# Multiplier.net
KiCad netlist of a schematic drawn in Altium Designer
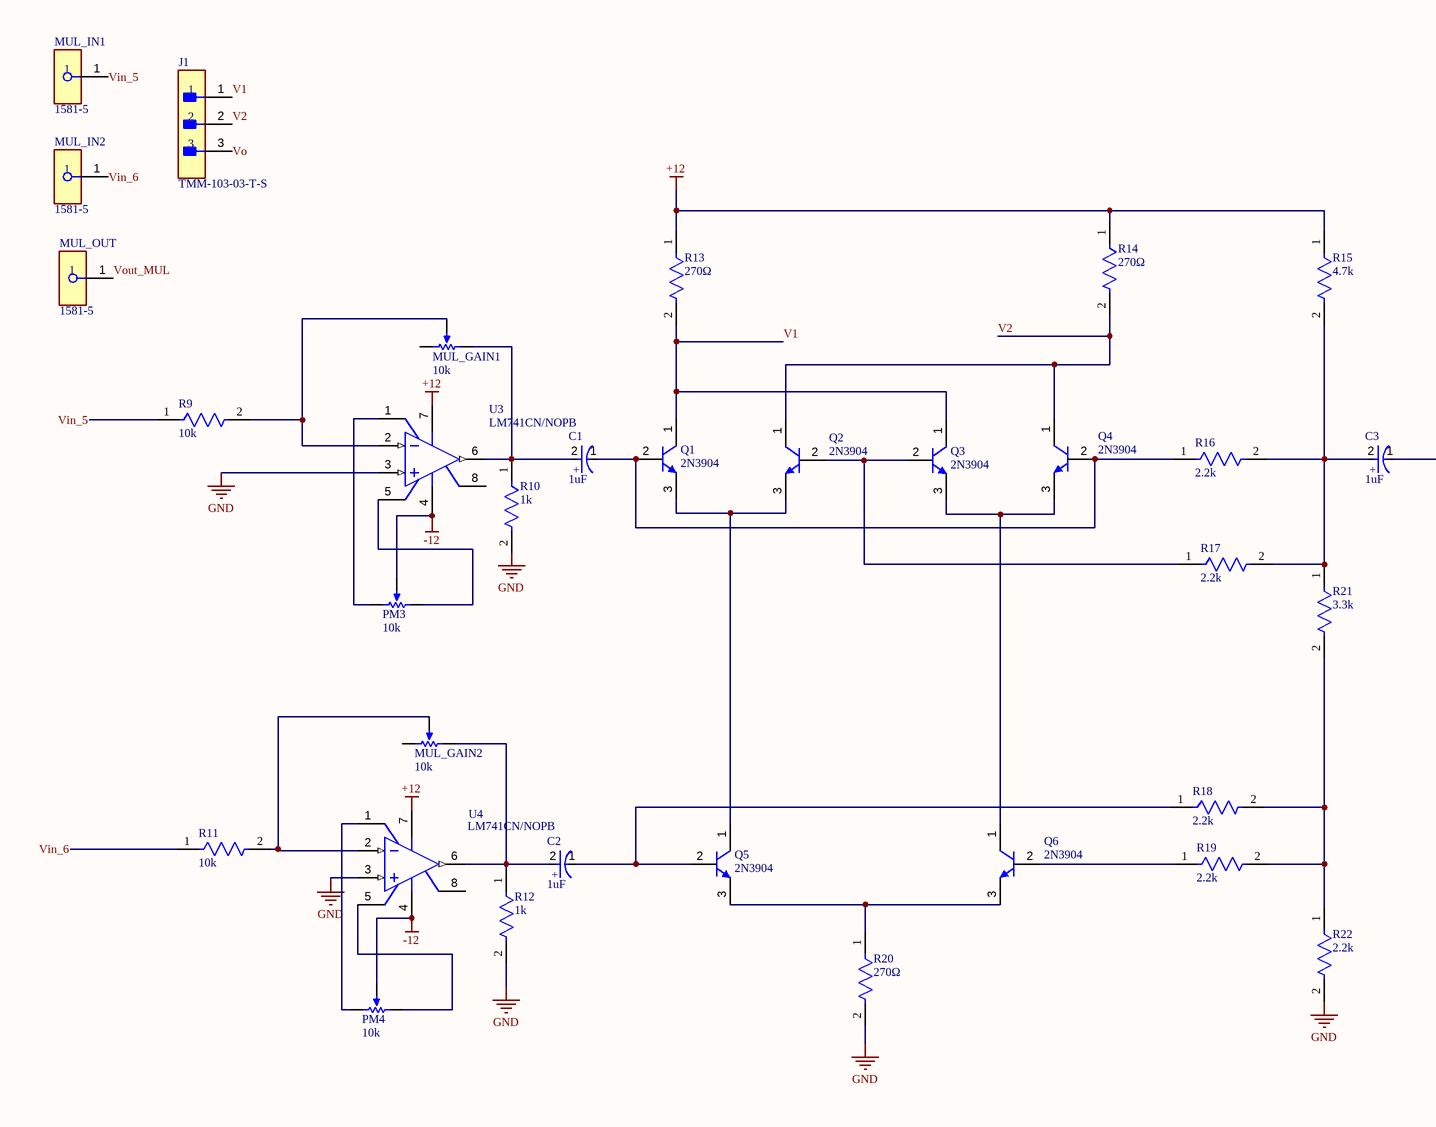
[diagram p0: Multiplier.SchDoc, left]
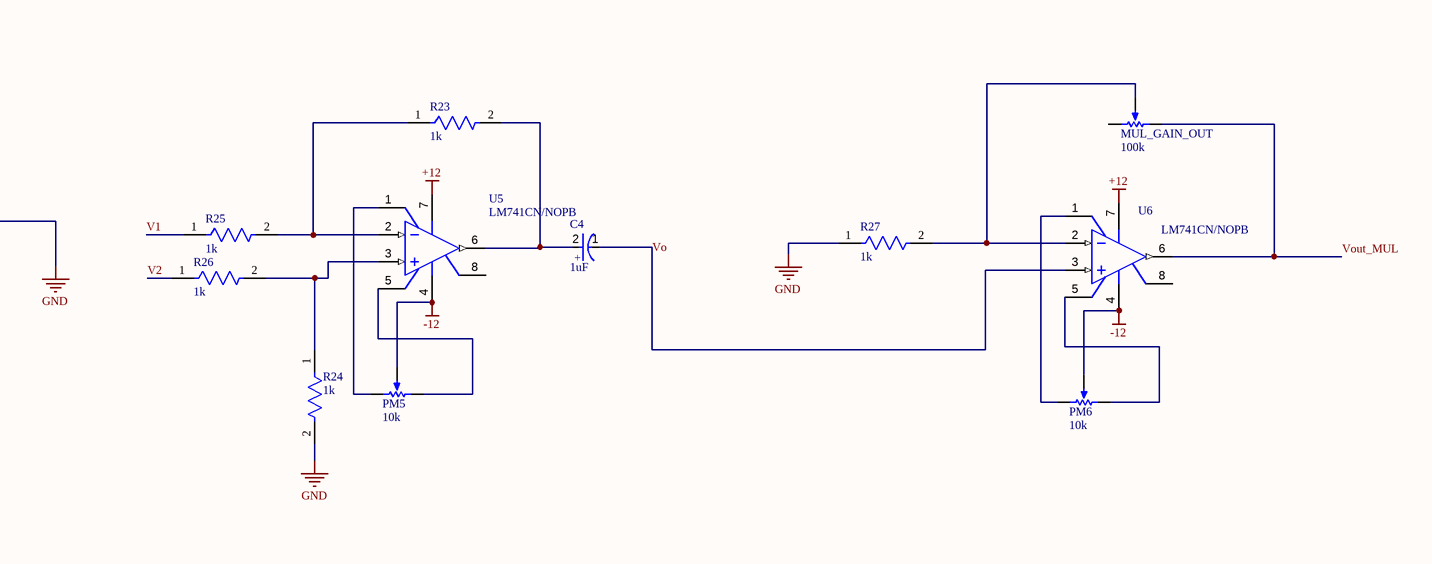
[diagram p1: Multiplier.SchDoc, right]

(export (version "E")
  (design (tool "Eeschema 10.0.6"))
  (components
    (comp (ref "C1")
      (value "1uF")
      (footprint "FP-ECA-2CHG010I-MFG")
      (description "CAP ALUM 1UF 20% 160V RADIAL")
      (fields (field (name "TOLERANCE") "20%"))
      (libsource (lib "Altium Content Vault") (part "a00bbbee19879c290e62620ae7e47b1"))
    )
    (comp (ref "C2")
      (value "1uF")
      (footprint "FP-ECA-2CHG010I-MFG")
      (description "CAP ALUM 1UF 20% 160V RADIAL")
      (fields (field (name "TOLERANCE") "20%"))
      (libsource (lib "Altium Content Vault") (part "a00bbbee19879c290e62620ae7e47b1"))
    )
    (comp (ref "C3")
      (value "1uF")
      (footprint "FP-ECA-2CHG010I-MFG")
      (description "CAP ALUM 1UF 20% 160V RADIAL")
      (fields (field (name "TOLERANCE") "20%"))
      (libsource (lib "Altium Content Vault") (part "a00bbbee19879c290e62620ae7e47b1"))
    )
    (comp (ref "C4")
      (value "1uF")
      (footprint "FP-ECA-2CHG010I-MFG")
      (description "CAP ALUM 1UF 20% 160V RADIAL")
      (fields (field (name "TOLERANCE") "20%"))
      (libsource (lib "Altium Content Vault") (part "a00bbbee19879c290e62620ae7e47b1"))
    )
    (comp (ref "J1")
      (value "TMM-103-03-T-S")
      (footprint "FP-TMM-103-03-T-S-MFG")
      (description "CONN HEADER VERT 3POS 2MM")
      (libsource (lib "Altium Content Vault") (part "0d3f023dd272f625e17a2be33dea85f"))
    )
    (comp (ref "MUL_GAIN1")
      (value "10k")
      (footprint "BOUR-3852A-282-103AL-3_V")
      (description "Diameter Panel Control, 10 KOhm, +/- 10%, 2 W, -1 to 125 degC, 3-Pin THD, RoHS, Bulk")
      (fields (field (name "TOLERANCE") "±10%") (field (name "MANUFACTURER") "Bourns"))
      (libsource (lib "Altium Content Vault") (part "RES-POT-3"))
    )
    (comp (ref "MUL_GAIN2")
      (value "10k")
      (footprint "BOUR-3852A-282-103AL-3_V")
      (description "Diameter Panel Control, 10 KOhm, +/- 10%, 2 W, -1 to 125 degC, 3-Pin THD, RoHS, Bulk")
      (fields (field (name "TOLERANCE") "±10%") (field (name "MANUFACTURER") "Bourns"))
      (libsource (lib "Altium Content Vault") (part "RES-POT-3"))
    )
    (comp (ref "MUL_GAIN_OUT")
      (value "100k")
      (footprint "BOUR-3852A-282-103AL-3_V")
      (description "Diameter Panel Control, 10 KOhm, +/- 10%, 2 W, -1 to 125 degC, 3-Pin THD, RoHS, Bulk")
      (fields (field (name "TOLERANCE") "±10%") (field (name "MANUFACTURER") "Bourns"))
      (libsource (lib "Altium Content Vault") (part "RES-POT-3"))
    )
    (comp (ref "MUL_IN1")
      (value "1581-5")
      (footprint "FP-1581-5-MFG")
      (description "CONN BANANA JACK TURRET GREEN")
      (libsource (lib "Altium Content Vault") (part "c5c826e0c4b67fe3b42ef77f2d4decc"))
    )
    (comp (ref "MUL_IN2")
      (value "1581-5")
      (footprint "FP-1581-5-MFG")
      (description "CONN BANANA JACK TURRET GREEN")
      (libsource (lib "Altium Content Vault") (part "c5c826e0c4b67fe3b42ef77f2d4decc"))
    )
    (comp (ref "MUL_OUT")
      (value "1581-5")
      (footprint "FP-1581-5-MFG")
      (description "CONN BANANA JACK TURRET GREEN")
      (libsource (lib "Altium Content Vault") (part "c5c826e0c4b67fe3b42ef77f2d4decc"))
    )
    (comp (ref "PM3")
      (value "10k")
      (footprint "BOUR-3362P")
      (description "Square Trimpot(R) Trimming Potentiometer, 10 KOhm, 300 V, -55 to 125 degC, 3-Pin THD, RoHS, Tube")
      (fields (field (name "TOLERANCE") "1%"))
      (libsource (lib "Altium Content Vault") (part "RES-POT-3"))
    )
    (comp (ref "PM4")
      (value "10k")
      (footprint "BOUR-3362P")
      (description "Square Trimpot(R) Trimming Potentiometer, 10 KOhm, 300 V, -55 to 125 degC, 3-Pin THD, RoHS, Tube")
      (fields (field (name "TOLERANCE") "1%"))
      (libsource (lib "Altium Content Vault") (part "RES-POT-3"))
    )
    (comp (ref "PM5")
      (value "10k")
      (footprint "BOUR-3362P")
      (description "Square Trimpot(R) Trimming Potentiometer, 10 KOhm, 300 V, -55 to 125 degC, 3-Pin THD, RoHS, Tube")
      (fields (field (name "TOLERANCE") "1%"))
      (libsource (lib "Altium Content Vault") (part "RES-POT-3"))
    )
    (comp (ref "PM6")
      (value "10k")
      (footprint "BOUR-3362P")
      (description "Square Trimpot(R) Trimming Potentiometer, 10 KOhm, 300 V, -55 to 125 degC, 3-Pin THD, RoHS, Tube")
      (fields (field (name "TOLERANCE") "1%"))
      (libsource (lib "Altium Content Vault") (part "RES-POT-3"))
    )
    (comp (ref "Q1")
      (value "2N3904")
      (footprint "ONSC-TO-92-3-29-11_AM_BL")
      (description "Amplifier Transistor, NPN Silicon, 3-Pin TO-92, Pb-Free, Tape and Reel - BC548BRL1G")
      (fields (field (name "MANUFACTURER") "On Semiconductor") (field (name "PARTNUMBER") "BC548BRL1G"))
      (libsource (lib "Altium Content Vault") (part "ONSC-NPN-C1B2E3-3"))
    )
    (comp (ref "Q2")
      (value "2N3904")
      (footprint "ONSC-TO-92-3-29-11_AM_BL")
      (description "Amplifier Transistor, NPN Silicon, 3-Pin TO-92, Pb-Free, Tape and Reel - BC548BRL1G")
      (fields (field (name "MANUFACTURER") "On Semiconductor") (field (name "PARTNUMBER") "BC548BRL1G"))
      (libsource (lib "Altium Content Vault") (part "ONSC-NPN-C1B2E3-3"))
    )
    (comp (ref "Q3")
      (value "2N3904")
      (footprint "ONSC-TO-92-3-29-11_AM_BL")
      (description "Amplifier Transistor, NPN Silicon, 3-Pin TO-92, Pb-Free, Tape and Reel - BC548BRL1G")
      (fields (field (name "MANUFACTURER") "On Semiconductor") (field (name "PARTNUMBER") "BC548BRL1G"))
      (libsource (lib "Altium Content Vault") (part "ONSC-NPN-C1B2E3-3"))
    )
    (comp (ref "Q4")
      (value "2N3904")
      (footprint "ONSC-TO-92-3-29-11_AM_BL")
      (description "Amplifier Transistor, NPN Silicon, 3-Pin TO-92, Pb-Free, Tape and Reel - BC548BRL1G")
      (fields (field (name "MANUFACTURER") "On Semiconductor") (field (name "PARTNUMBER") "BC548BRL1G"))
      (libsource (lib "Altium Content Vault") (part "ONSC-NPN-C1B2E3-3"))
    )
    (comp (ref "Q5")
      (value "2N3904")
      (footprint "ONSC-TO-92-3-29-11_AM_BL")
      (description "Amplifier Transistor, NPN Silicon, 3-Pin TO-92, Pb-Free, Tape and Reel - BC548BRL1G")
      (fields (field (name "MANUFACTURER") "On Semiconductor") (field (name "PARTNUMBER") "BC548BRL1G"))
      (libsource (lib "Altium Content Vault") (part "ONSC-NPN-C1B2E3-3"))
    )
    (comp (ref "Q6")
      (value "2N3904")
      (footprint "ONSC-TO-92-3-29-11_AM_BL")
      (description "Amplifier Transistor, NPN Silicon, 3-Pin TO-92, Pb-Free, Tape and Reel - BC548BRL1G")
      (fields (field (name "MANUFACTURER") "On Semiconductor") (field (name "PARTNUMBER") "BC548BRL1G"))
      (libsource (lib "Altium Content Vault") (part "ONSC-NPN-C1B2E3-3"))
    )
    (comp (ref "R9")
      (value "10k")
      (footprint "FP-RLR07-MFG")
      (fields (field (name "TOLERANCE") "1%"))
      (libsource (lib "Altium Content Vault") (part "1029c3af85768c4190bb7ad29bc67b5"))
    )
    (comp (ref "R10")
      (value "1k")
      (footprint "FP-RLR07-MFG")
      (fields (field (name "TOLERANCE") "1%"))
      (libsource (lib "Altium Content Vault") (part "1029c3af85768c4190bb7ad29bc67b5"))
    )
    (comp (ref "R11")
      (value "10k")
      (footprint "FP-RLR07-MFG")
      (fields (field (name "TOLERANCE") "1%"))
      (libsource (lib "Altium Content Vault") (part "1029c3af85768c4190bb7ad29bc67b5"))
    )
    (comp (ref "R12")
      (value "1k")
      (footprint "FP-RLR07-MFG")
      (fields (field (name "TOLERANCE") "1%"))
      (libsource (lib "Altium Content Vault") (part "1029c3af85768c4190bb7ad29bc67b5"))
    )
    (comp (ref "R13")
      (value "270Ω")
      (footprint "FP-RLR07-MFG")
      (fields (field (name "TOLERANCE") "1%"))
      (libsource (lib "Altium Content Vault") (part "1029c3af85768c4190bb7ad29bc67b5"))
    )
    (comp (ref "R14")
      (value "270Ω")
      (footprint "FP-RLR07-MFG")
      (fields (field (name "TOLERANCE") "1%"))
      (libsource (lib "Altium Content Vault") (part "1029c3af85768c4190bb7ad29bc67b5"))
    )
    (comp (ref "R15")
      (value "4.7k")
      (footprint "FP-RLR07-MFG")
      (fields (field (name "TOLERANCE") "1%"))
      (libsource (lib "Altium Content Vault") (part "1029c3af85768c4190bb7ad29bc67b5"))
    )
    (comp (ref "R16")
      (value "2.2k")
      (footprint "FP-RLR07-MFG")
      (fields (field (name "TOLERANCE") "1%"))
      (libsource (lib "Altium Content Vault") (part "1029c3af85768c4190bb7ad29bc67b5"))
    )
    (comp (ref "R17")
      (value "2.2k")
      (footprint "FP-RLR07-MFG")
      (fields (field (name "TOLERANCE") "1%"))
      (libsource (lib "Altium Content Vault") (part "1029c3af85768c4190bb7ad29bc67b5"))
    )
    (comp (ref "R18")
      (value "2.2k")
      (footprint "FP-RLR07-MFG")
      (fields (field (name "TOLERANCE") "1%"))
      (libsource (lib "Altium Content Vault") (part "1029c3af85768c4190bb7ad29bc67b5"))
    )
    (comp (ref "R19")
      (value "2.2k")
      (footprint "FP-RLR07-MFG")
      (fields (field (name "TOLERANCE") "1%"))
      (libsource (lib "Altium Content Vault") (part "1029c3af85768c4190bb7ad29bc67b5"))
    )
    (comp (ref "R20")
      (value "270Ω")
      (footprint "FP-RLR07-MFG")
      (fields (field (name "TOLERANCE") "1%"))
      (libsource (lib "Altium Content Vault") (part "1029c3af85768c4190bb7ad29bc67b5"))
    )
    (comp (ref "R21")
      (value "3.3k")
      (footprint "FP-RLR07-MFG")
      (fields (field (name "TOLERANCE") "1%"))
      (libsource (lib "Altium Content Vault") (part "1029c3af85768c4190bb7ad29bc67b5"))
    )
    (comp (ref "R22")
      (value "2.2k")
      (footprint "FP-RLR07-MFG")
      (fields (field (name "TOLERANCE") "1%"))
      (libsource (lib "Altium Content Vault") (part "1029c3af85768c4190bb7ad29bc67b5"))
    )
    (comp (ref "R23")
      (value "1k")
      (footprint "FP-RLR07-MFG")
      (fields (field (name "TOLERANCE") "1%"))
      (libsource (lib "Altium Content Vault") (part "1029c3af85768c4190bb7ad29bc67b5"))
    )
    (comp (ref "R24")
      (value "1k")
      (footprint "FP-RLR07-MFG")
      (fields (field (name "TOLERANCE") "1%"))
      (libsource (lib "Altium Content Vault") (part "1029c3af85768c4190bb7ad29bc67b5"))
    )
    (comp (ref "R25")
      (value "1k")
      (footprint "FP-RLR07-MFG")
      (fields (field (name "TOLERANCE") "1%"))
      (libsource (lib "Altium Content Vault") (part "1029c3af85768c4190bb7ad29bc67b5"))
    )
    (comp (ref "R26")
      (value "1k")
      (footprint "FP-RLR07-MFG")
      (fields (field (name "TOLERANCE") "1%"))
      (libsource (lib "Altium Content Vault") (part "1029c3af85768c4190bb7ad29bc67b5"))
    )
    (comp (ref "R27")
      (value "1k")
      (footprint "FP-RLR07-MFG")
      (fields (field (name "TOLERANCE") "1%"))
      (libsource (lib "Altium Content Vault") (part "1029c3af85768c4190bb7ad29bc67b5"))
    )
    (comp (ref "U3")
      (value "LM741CN/NOPB")
      (footprint "P0008A")
      (description "Operational Amplifier, 8-pin MDIP, Pb-Free")
      (fields (field (name "MANUFACTURER") "Texas Instruments"))
      (libsource (lib "Altium Content Vault") (part "AMP-OPA-LM741-8"))
    )
    (comp (ref "U4")
      (value "LM741CN/NOPB")
      (footprint "P0008A")
      (description "Operational Amplifier, 8-pin MDIP, Pb-Free")
      (fields (field (name "MANUFACTURER") "Texas Instruments"))
      (libsource (lib "Altium Content Vault") (part "AMP-OPA-LM741-8"))
    )
    (comp (ref "U5")
      (value "LM741CN/NOPB")
      (footprint "P0008A")
      (description "Operational Amplifier, 8-pin MDIP, Pb-Free")
      (fields (field (name "MANUFACTURER") "Texas Instruments"))
      (libsource (lib "Altium Content Vault") (part "AMP-OPA-LM741-8"))
    )
    (comp (ref "U6")
      (value "LM741CN/NOPB")
      (footprint "P0008A")
      (description "Operational Amplifier, 8-pin MDIP, Pb-Free")
      (fields (field (name "MANUFACTURER") "Texas Instruments"))
      (libsource (lib "Altium Content Vault") (part "AMP-OPA-LM741-8"))
    )
  )
  (nets
    (net (code "1") (name "+12") (class "Default")
      (node (ref "R13") (pin "1") (pinfunction "1_1") (pintype "passive"))
      (node (ref "R14") (pin "1") (pinfunction "1_1") (pintype "passive"))
      (node (ref "R15") (pin "1") (pinfunction "1_1") (pintype "passive"))
      (node (ref "U3") (pin "7") (pinfunction "V+_7") (pintype "power_in"))
      (node (ref "U4") (pin "7") (pinfunction "V+_7") (pintype "power_in"))
      (node (ref "U5") (pin "7") (pinfunction "V+_7") (pintype "power_in"))
      (node (ref "U6") (pin "7") (pinfunction "V+_7") (pintype "power_in"))
    )
    (net (code "2") (name "-12") (class "Default")
      (node (ref "PM3") (pin "2") (pinfunction "S_2") (pintype "passive"))
      (node (ref "PM4") (pin "2") (pinfunction "S_2") (pintype "passive"))
      (node (ref "PM5") (pin "2") (pinfunction "S_2") (pintype "passive"))
      (node (ref "PM6") (pin "2") (pinfunction "S_2") (pintype "passive"))
      (node (ref "U3") (pin "4") (pinfunction "V-_4") (pintype "power_in"))
      (node (ref "U4") (pin "4") (pinfunction "V-_4") (pintype "power_in"))
      (node (ref "U5") (pin "4") (pinfunction "V-_4") (pintype "power_in"))
      (node (ref "U6") (pin "4") (pinfunction "V-_4") (pintype "power_in"))
    )
    (net (code "3") (name "/V1") (class "Default")
      (node (ref "J1") (pin "1") (pinfunction "1_1") (pintype "passive"))
      (node (ref "Q1") (pin "1") (pinfunction "C_1") (pintype "passive"))
      (node (ref "Q3") (pin "1") (pinfunction "C_1") (pintype "passive"))
      (node (ref "R13") (pin "2") (pinfunction "2_2") (pintype "passive"))
      (node (ref "R25") (pin "1") (pinfunction "1_1") (pintype "passive"))
    )
    (net (code "4") (name "/V2") (class "Default")
      (node (ref "J1") (pin "2") (pinfunction "2_2") (pintype "passive"))
      (node (ref "Q2") (pin "1") (pinfunction "C_1") (pintype "passive"))
      (node (ref "Q4") (pin "1") (pinfunction "C_1") (pintype "passive"))
      (node (ref "R14") (pin "2") (pinfunction "2_2") (pintype "passive"))
      (node (ref "R26") (pin "1") (pinfunction "1_1") (pintype "passive"))
    )
    (net (code "5") (name "/Vin_5") (class "Default")
      (node (ref "MUL_IN1") (pin "1") (pinfunction "1_1") (pintype "passive"))
      (node (ref "R9") (pin "1") (pinfunction "1_1") (pintype "passive"))
    )
    (net (code "6") (name "/Vin_6") (class "Default")
      (node (ref "MUL_IN2") (pin "1") (pinfunction "1_1") (pintype "passive"))
      (node (ref "R11") (pin "1") (pinfunction "1_1") (pintype "passive"))
    )
    (net (code "7") (name "/Vo") (class "Default")
      (node (ref "C4") (pin "1") (pinfunction "C_1") (pintype "passive"))
      (node (ref "J1") (pin "3") (pinfunction "3_3") (pintype "passive"))
      (node (ref "U6") (pin "3") (pinfunction "IN+_3") (pintype "input"))
    )
    (net (code "8") (name "/Vout_MUL") (class "Default")
      (node (ref "MUL_GAIN_OUT") (pin "1") (pinfunction "CCW_1") (pintype "passive"))
      (node (ref "MUL_OUT") (pin "1") (pinfunction "1_1") (pintype "passive"))
      (node (ref "U6") (pin "6") (pinfunction "OUT_6") (pintype "output"))
    )
    (net (code "9") (name "GND") (class "Default")
      (node (ref "C3") (pin "1") (pinfunction "C_1") (pintype "passive"))
      (node (ref "R10") (pin "2") (pinfunction "2_2") (pintype "passive"))
      (node (ref "R12") (pin "2") (pinfunction "2_2") (pintype "passive"))
      (node (ref "R20") (pin "2") (pinfunction "2_2") (pintype "passive"))
      (node (ref "R22") (pin "2") (pinfunction "2_2") (pintype "passive"))
      (node (ref "R24") (pin "2") (pinfunction "2_2") (pintype "passive"))
      (node (ref "R27") (pin "1") (pinfunction "1_1") (pintype "passive"))
      (node (ref "U3") (pin "3") (pinfunction "IN+_3") (pintype "input"))
      (node (ref "U4") (pin "3") (pinfunction "IN+_3") (pintype "input"))
    )
    (net (code "10") (name "Net-(C1-A)") (class "Default")
      (node (ref "C1") (pin "2") (pinfunction "A_2") (pintype "passive"))
      (node (ref "MUL_GAIN1") (pin "1") (pinfunction "CCW_1") (pintype "passive"))
      (node (ref "R10") (pin "1") (pinfunction "1_1") (pintype "passive"))
      (node (ref "U3") (pin "6") (pinfunction "OUT_6") (pintype "output"))
    )
    (net (code "11") (name "Net-(C1-C)") (class "Default")
      (node (ref "C1") (pin "1") (pinfunction "C_1") (pintype "passive"))
      (node (ref "Q1") (pin "2") (pinfunction "B_2") (pintype "passive"))
      (node (ref "Q4") (pin "2") (pinfunction "B_2") (pintype "passive"))
      (node (ref "R16") (pin "1") (pinfunction "1_1") (pintype "passive"))
    )
    (net (code "12") (name "Net-(C2-A)") (class "Default")
      (node (ref "C2") (pin "2") (pinfunction "A_2") (pintype "passive"))
      (node (ref "MUL_GAIN2") (pin "1") (pinfunction "CCW_1") (pintype "passive"))
      (node (ref "R12") (pin "1") (pinfunction "1_1") (pintype "passive"))
      (node (ref "U4") (pin "6") (pinfunction "OUT_6") (pintype "output"))
    )
    (net (code "13") (name "Net-(C2-C)") (class "Default")
      (node (ref "C2") (pin "1") (pinfunction "C_1") (pintype "passive"))
      (node (ref "Q5") (pin "2") (pinfunction "B_2") (pintype "passive"))
      (node (ref "R18") (pin "1") (pinfunction "1_1") (pintype "passive"))
    )
    (net (code "14") (name "Net-(C3-A)") (class "Default")
      (node (ref "C3") (pin "2") (pinfunction "A_2") (pintype "passive"))
      (node (ref "R15") (pin "2") (pinfunction "2_2") (pintype "passive"))
      (node (ref "R16") (pin "2") (pinfunction "2_2") (pintype "passive"))
      (node (ref "R17") (pin "2") (pinfunction "2_2") (pintype "passive"))
      (node (ref "R21") (pin "1") (pinfunction "1_1") (pintype "passive"))
    )
    (net (code "15") (name "Net-(C4-A)") (class "Default")
      (node (ref "C4") (pin "2") (pinfunction "A_2") (pintype "passive"))
      (node (ref "R23") (pin "2") (pinfunction "2_2") (pintype "passive"))
      (node (ref "U5") (pin "6") (pinfunction "OUT_6") (pintype "output"))
    )
    (net (code "16") (name "Net-(MUL_GAIN1-S)") (class "Default")
      (node (ref "MUL_GAIN1") (pin "2") (pinfunction "S_2") (pintype "passive"))
      (node (ref "R9") (pin "2") (pinfunction "2_2") (pintype "passive"))
      (node (ref "U3") (pin "2") (pinfunction "IN-_2") (pintype "input"))
    )
    (net (code "17") (name "Net-(MUL_GAIN2-S)") (class "Default")
      (node (ref "MUL_GAIN2") (pin "2") (pinfunction "S_2") (pintype "passive"))
      (node (ref "R11") (pin "2") (pinfunction "2_2") (pintype "passive"))
      (node (ref "U4") (pin "2") (pinfunction "IN-_2") (pintype "input"))
    )
    (net (code "18") (name "Net-(MUL_GAIN_OUT-S)") (class "Default")
      (node (ref "MUL_GAIN_OUT") (pin "2") (pinfunction "S_2") (pintype "passive"))
      (node (ref "R27") (pin "2") (pinfunction "2_2") (pintype "passive"))
      (node (ref "U6") (pin "2") (pinfunction "IN-_2") (pintype "input"))
    )
    (net (code "19") (name "Net-(PM3-CCW)") (class "Default")
      (node (ref "PM3") (pin "1") (pinfunction "CCW_1") (pintype "passive"))
      (node (ref "U3") (pin "5") (pinfunction "OFS_NULL_5") (pintype "passive"))
    )
    (net (code "20") (name "Net-(PM3-CW)") (class "Default")
      (node (ref "PM3") (pin "3") (pinfunction "CW_3") (pintype "passive"))
      (node (ref "U3") (pin "1") (pinfunction "OFS_NULL_1") (pintype "passive"))
    )
    (net (code "21") (name "Net-(PM4-CCW)") (class "Default")
      (node (ref "PM4") (pin "1") (pinfunction "CCW_1") (pintype "passive"))
      (node (ref "U4") (pin "5") (pinfunction "OFS_NULL_5") (pintype "passive"))
    )
    (net (code "22") (name "Net-(PM4-CW)") (class "Default")
      (node (ref "PM4") (pin "3") (pinfunction "CW_3") (pintype "passive"))
      (node (ref "U4") (pin "1") (pinfunction "OFS_NULL_1") (pintype "passive"))
    )
    (net (code "23") (name "Net-(PM5-CCW)") (class "Default")
      (node (ref "PM5") (pin "1") (pinfunction "CCW_1") (pintype "passive"))
      (node (ref "U5") (pin "5") (pinfunction "OFS_NULL_5") (pintype "passive"))
    )
    (net (code "24") (name "Net-(PM5-CW)") (class "Default")
      (node (ref "PM5") (pin "3") (pinfunction "CW_3") (pintype "passive"))
      (node (ref "U5") (pin "1") (pinfunction "OFS_NULL_1") (pintype "passive"))
    )
    (net (code "25") (name "Net-(PM6-CCW)") (class "Default")
      (node (ref "PM6") (pin "1") (pinfunction "CCW_1") (pintype "passive"))
      (node (ref "U6") (pin "5") (pinfunction "OFS_NULL_5") (pintype "passive"))
    )
    (net (code "26") (name "Net-(PM6-CW)") (class "Default")
      (node (ref "PM6") (pin "3") (pinfunction "CW_3") (pintype "passive"))
      (node (ref "U6") (pin "1") (pinfunction "OFS_NULL_1") (pintype "passive"))
    )
    (net (code "27") (name "Net-(Q1-E)") (class "Default")
      (node (ref "Q1") (pin "3") (pinfunction "E_3") (pintype "passive"))
      (node (ref "Q2") (pin "3") (pinfunction "E_3") (pintype "passive"))
      (node (ref "Q5") (pin "1") (pinfunction "C_1") (pintype "passive"))
    )
    (net (code "28") (name "Net-(Q2-B)") (class "Default")
      (node (ref "Q2") (pin "2") (pinfunction "B_2") (pintype "passive"))
      (node (ref "Q3") (pin "2") (pinfunction "B_2") (pintype "passive"))
      (node (ref "R17") (pin "1") (pinfunction "1_1") (pintype "passive"))
    )
    (net (code "29") (name "Net-(Q3-E)") (class "Default")
      (node (ref "Q3") (pin "3") (pinfunction "E_3") (pintype "passive"))
      (node (ref "Q4") (pin "3") (pinfunction "E_3") (pintype "passive"))
      (node (ref "Q6") (pin "1") (pinfunction "C_1") (pintype "passive"))
    )
    (net (code "30") (name "Net-(Q5-E)") (class "Default")
      (node (ref "Q5") (pin "3") (pinfunction "E_3") (pintype "passive"))
      (node (ref "Q6") (pin "3") (pinfunction "E_3") (pintype "passive"))
      (node (ref "R20") (pin "1") (pinfunction "1_1") (pintype "passive"))
    )
    (net (code "31") (name "Net-(Q6-B)") (class "Default")
      (node (ref "Q6") (pin "2") (pinfunction "B_2") (pintype "passive"))
      (node (ref "R19") (pin "1") (pinfunction "1_1") (pintype "passive"))
    )
    (net (code "32") (name "Net-(R18-Pad2)") (class "Default")
      (node (ref "R18") (pin "2") (pinfunction "2_2") (pintype "passive"))
      (node (ref "R19") (pin "2") (pinfunction "2_2") (pintype "passive"))
      (node (ref "R21") (pin "2") (pinfunction "2_2") (pintype "passive"))
      (node (ref "R22") (pin "1") (pinfunction "1_1") (pintype "passive"))
    )
    (net (code "33") (name "Net-(U5-IN+)") (class "Default")
      (node (ref "R24") (pin "1") (pinfunction "1_1") (pintype "passive"))
      (node (ref "R26") (pin "2") (pinfunction "2_2") (pintype "passive"))
      (node (ref "U5") (pin "3") (pinfunction "IN+_3") (pintype "input"))
    )
    (net (code "34") (name "Net-(U5-IN-)") (class "Default")
      (node (ref "R23") (pin "1") (pinfunction "1_1") (pintype "passive"))
      (node (ref "R25") (pin "2") (pinfunction "2_2") (pintype "passive"))
      (node (ref "U5") (pin "2") (pinfunction "IN-_2") (pintype "input"))
    )
    (net (code "35") (name "unconnected-(MUL_GAIN1-CW-Pad3)") (class "Default")
      (node (ref "MUL_GAIN1") (pin "3") (pinfunction "CW_3") (pintype "passive"))
    )
    (net (code "36") (name "unconnected-(MUL_GAIN2-CW-Pad3)") (class "Default")
      (node (ref "MUL_GAIN2") (pin "3") (pinfunction "CW_3") (pintype "passive"))
    )
    (net (code "37") (name "unconnected-(MUL_GAIN_OUT-CW-Pad3)") (class "Default")
      (node (ref "MUL_GAIN_OUT") (pin "3") (pinfunction "CW_3") (pintype "passive"))
    )
    (net (code "38") (name "unconnected-(U3-NC-Pad8)") (class "Default")
      (node (ref "U3") (pin "8") (pinfunction "NC_8") (pintype "passive"))
    )
    (net (code "39") (name "unconnected-(U4-NC-Pad8)") (class "Default")
      (node (ref "U4") (pin "8") (pinfunction "NC_8") (pintype "passive"))
    )
    (net (code "40") (name "unconnected-(U5-NC-Pad8)") (class "Default")
      (node (ref "U5") (pin "8") (pinfunction "NC_8") (pintype "passive"))
    )
    (net (code "41") (name "unconnected-(U6-NC-Pad8)") (class "Default")
      (node (ref "U6") (pin "8") (pinfunction "NC_8") (pintype "passive"))
    )
  )
)
